# NixiePSU.net
KiCad netlist of a schematic drawn in Altium Designer
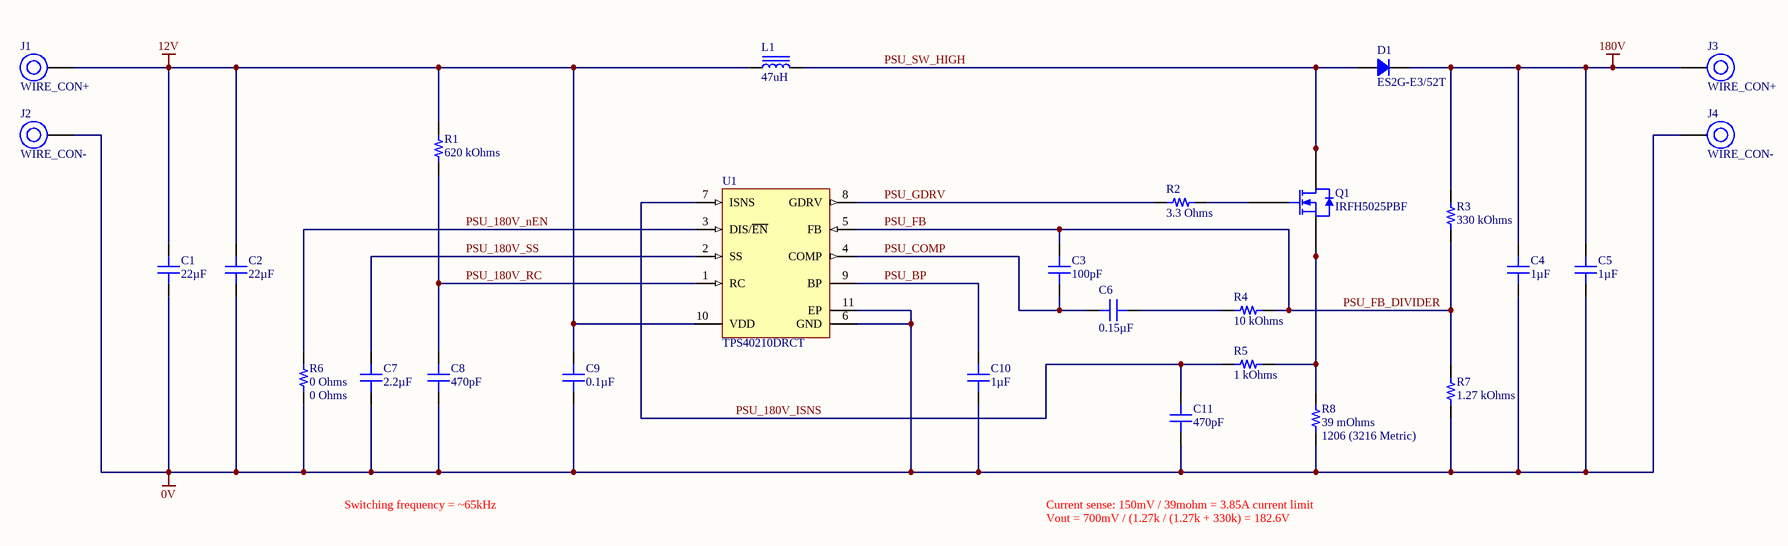
[diagram p0: NixiePSU.SchDoc]

(export (version "E")
  (design (tool "Eeschema 10.0.6"))
  (components
    (comp (ref "C1")
      (value "22µF")
      (footprint "CAP 1210_3225 - 2.8MM")
      (description "CAP CER 22UF 25V X6S 1210")
      (fields (field (name "PART NUMBER") "GRM32EC81E226KE15L"))
      (libsource (lib "Celestial Altium Library - altium_library") (part "Capacitor"))
    )
    (comp (ref "C2")
      (value "22µF")
      (footprint "CAP 1210_3225 - 2.8MM")
      (description "CAP CER 22UF 25V X6S 1210")
      (fields (field (name "PART NUMBER") "GRM32EC81E226KE15L"))
      (libsource (lib "Celestial Altium Library - altium_library") (part "Capacitor"))
    )
    (comp (ref "C3")
      (value "100pF")
      (footprint "CAP 0603_1608")
      (description "CAP CER 100PF 16V NP0 0603")
      (fields (field (name "PART NUMBER") "C0603C101K4GAC7867") (field (name "MANUFACTURER") "KEMET"))
      (libsource (lib "Celestial Altium Library - altium_library") (part "Capacitor"))
    )
    (comp (ref "C4")
      (value "1µF")
      (footprint "CAP 2220_5650 2.0MM")
      (description "CAP CER 1UF 250V X7R 2220")
      (fields (field (name "PART NUMBER") "C2220C105KARACTU") (field (name "MANUFACTURER") "KEMET"))
      (libsource (lib "Celestial Altium Library - altium_library") (part "Capacitor"))
    )
    (comp (ref "C5")
      (value "1µF")
      (footprint "CAP 2220_5650 2.0MM")
      (description "CAP CER 1UF 250V X7R 2220")
      (fields (field (name "PART NUMBER") "C2220C105KARACTU") (field (name "MANUFACTURER") "KEMET"))
      (libsource (lib "Celestial Altium Library - altium_library") (part "Capacitor"))
    )
    (comp (ref "C6")
      (value "0.15µF")
      (footprint "CAP 0603_1608")
      (description "CAP CER 0.15UF 16V X7R 0603")
      (fields (field (name "PART NUMBER") "CC0603KRX7R7BB154") (field (name "MANUFACTURER") "Yageo"))
      (libsource (lib "Celestial Altium Library - altium_library") (part "Capacitor"))
    )
    (comp (ref "C7")
      (value "2.2µF")
      (footprint "CAP 0603_1608")
      (description "CAP CER 2.2UF 50V X5R 0603")
      (fields (field (name "PART NUMBER") "GRM188R61H225KE11D"))
      (libsource (lib "Celestial Altium Library - altium_library") (part "Capacitor"))
    )
    (comp (ref "C8")
      (value "470pF")
      (footprint "CAP 0603_1608")
      (description "CAP CER 470PF 50V C0G 0603")
      (fields (field (name "PART NUMBER") "CGJ3E2C0G1H471J080AA"))
      (libsource (lib "Celestial Altium Library - altium_library") (part "Capacitor"))
    )
    (comp (ref "C9")
      (value "0.1µF")
      (footprint "CAP 0603_1608")
      (description "CAP CER 0.1UF 25V X5R 0603")
      (fields (field (name "PART NUMBER") "C0603C104K3PAC7867") (field (name "MANUFACTURER") "KEMET"))
      (libsource (lib "Celestial Altium Library - altium_library") (part "Capacitor"))
    )
    (comp (ref "C10")
      (value "1µF")
      (footprint "CAP 0603_1608")
      (description "CAP CER 1UF 25V X7R 0603")
      (fields
        (field (name "PART NUMBER") "CGJ3E1X7R1E105K080AC")
        (field (name "MANUFACTURER") "TDK Corporation")
      )
      (libsource (lib "Celestial Altium Library - altium_library") (part "Capacitor"))
    )
    (comp (ref "C11")
      (value "470pF")
      (footprint "CAP 0603_1608")
      (description "CAP CER 470PF 50V C0G 0603")
      (fields (field (name "PART NUMBER") "CGJ3E2C0G1H471J080AA"))
      (libsource (lib "Celestial Altium Library - altium_library") (part "Capacitor"))
    )
    (comp (ref "D1")
      (value "ES2G-E3/52T")
      (footprint "DO214AA SMB")
      (description "DIODE GEN PURP 400V 2A DO214AA")
      (fields (field (name "MANUFACTURER") "Vishay Semiconductor Diodes Division"))
      (libsource (lib "Celestial Altium Library - altium_library") (part "Diode"))
    )
    (comp (ref "J1")
      (value "WIRE_CON+")
      (footprint "WIRE_PAD+")
      (description "Wire pad connection")
      (libsource (lib "Connectors") (part "WIRE_CON+"))
    )
    (comp (ref "J2")
      (value "WIRE_CON-")
      (footprint "WIRE_PAD-")
      (description "Wire pad connection")
      (libsource (lib "Connectors") (part "WIRE_CON-"))
    )
    (comp (ref "J3")
      (value "WIRE_CON+")
      (footprint "WIRE_PAD+")
      (description "Wire pad connection")
      (libsource (lib "Connectors") (part "WIRE_CON+"))
    )
    (comp (ref "J4")
      (value "WIRE_CON-")
      (footprint "WIRE_PAD-")
      (description "Wire pad connection")
      (libsource (lib "Connectors") (part "WIRE_CON-"))
    )
    (comp (ref "L1")
      (value "47uH")
      (footprint "SRP1040VA")
      (description "FIXED IND 47UH 4A 167MOHM SMD")
      (libsource (lib "NixiePSU") (part "SRP1040VA-470M"))
    )
    (comp (ref "Q1")
      (value "IRFH5025PBF")
      (footprint "QFN127P600X500X80_HS-9M")
      (description "IRFH5025TRPBF -  MOSFET Transistor, N Channel, 25 A, 250 V, 0.084 ohm, 10 V, 5 V")
      (libsource (lib "Transistors") (part "IRFH5025PBF N Channel FET"))
    )
    (comp (ref "R1")
      (value "620 kOhms")
      (footprint "RES 0603_1608")
      (description "RES SMD 620K OHM 1% 1/10W 0603")
      (fields (field (name "PART NUMBER") "ERJ-3EKF6203V"))
      (libsource (lib "Celestial Altium Library - altium_library") (part "Resistor"))
    )
    (comp (ref "R2")
      (value "3.3 Ohms")
      (footprint "RES 0603_1608")
      (description "RES SMD 3.3 OHM 1% 1/10W 0603")
      (fields
        (field (name "PART NUMBER") "ERJ-3RQF3R3V")
        (field (name "MANUFACTURER") "Panasonic Electronic Components")
      )
      (libsource (lib "Celestial Altium Library - altium_library") (part "Resistor"))
    )
    (comp (ref "R3")
      (value "330 kOhms")
      (footprint "RES 0603_1608")
      (description "RES SMD 330K OHM 1% 1/10W 0603")
      (fields
        (field (name "PART NUMBER") "ERJ-3EKF3303V")
        (field (name "MANUFACTURER") "Panasonic Electronic Components")
      )
      (libsource (lib "Celestial Altium Library - altium_library") (part "Resistor"))
    )
    (comp (ref "R4")
      (value "10 kOhms")
      (footprint "RES 0603_1608")
      (description "RES SMD 10K OHM 1% 1/10W 0603")
      (fields
        (field (name "PART NUMBER") "ERJ-3EKF1002V")
        (field (name "MANUFACTURER") "Panasonic Electronic Components")
      )
      (libsource (lib "Celestial Altium Library - altium_library") (part "Resistor"))
    )
    (comp (ref "R5")
      (value "1 kOhms")
      (footprint "RES 0603_1608")
      (description "RES SMD 1K OHM 1% 1/10W 0603")
      (fields
        (field (name "PART NUMBER") "ERJ-3EKF1001V")
        (field (name "MANUFACTURER") "Panasonic Electronic Components")
      )
      (libsource (lib "Celestial Altium Library - altium_library") (part "Resistor"))
    )
    (comp (ref "R6")
      (value "0 Ohms")
      (footprint "RES 0603_1608")
      (description "RES 0 OHM JUMPER 0.01W 0603")
      (fields (field (name "PART NUMBER") "CR0603-J/-000EAS") (field (name "ALTIUM_VALUE") "0 Ohms"))
      (libsource (lib "Celestial Altium Library - altium_library") (part "Resistor"))
    )
    (comp (ref "R7")
      (value "1.27 kOhms")
      (footprint "RES 0603_1608")
      (description "RES SMD 1.27K OHM 1% 1/10W 0603")
      (fields
        (field (name "PART NUMBER") "ERJ-3EKF1271V")
        (field (name "MANUFACTURER") "Panasonic Electronic Components")
      )
      (libsource (lib "Celestial Altium Library - altium_library") (part "Resistor"))
    )
    (comp (ref "R8")
      (value "39 mOhms")
      (footprint "STACKPOLE CSR1206")
      (description "RES 0.039 OHM 1% 1W 1206")
      (fields
        (field (name "PART NUMBER") "ERJ-8BWFR039V")
        (field (name "PACKAGE / CASE") "1206 (3216 Metric)")
        (field (name "MANUFACTURER") "Panasonic Electronic Components")
      )
      (libsource (lib "Celestial Altium Library - altium_library") (part "Resistor"))
    )
    (comp (ref "U1")
      (value "TPS40210DRCT")
      (footprint "DRC0010A_V")
      (fields (field (name "MANUFACTURER") "Texas Instruments"))
      (libsource (lib "Altium Content Vault") (part "TI-TPS40210DRC10-2400X1650TP"))
    )
  )
  (nets
    (net (code "1") (name "/PSU_180V_ISNS") (class "Default")
      (node (ref "C11") (pin "2") (pinfunction "2_2") (pintype "passive"))
      (node (ref "R5") (pin "1") (pinfunction "1_1") (pintype "passive"))
      (node (ref "U1") (pin "7") (pinfunction "ISNS_7") (pintype "input"))
    )
    (net (code "2") (name "/PSU_180V_RC") (class "Default")
      (node (ref "C8") (pin "2") (pinfunction "2_2") (pintype "passive"))
      (node (ref "R1") (pin "1") (pinfunction "1_1") (pintype "passive"))
      (node (ref "U1") (pin "1") (pinfunction "RC_1") (pintype "input"))
    )
    (net (code "3") (name "/PSU_180V_SS") (class "Default")
      (node (ref "C7") (pin "2") (pinfunction "2_2") (pintype "passive"))
      (node (ref "U1") (pin "2") (pinfunction "SS_2") (pintype "input"))
    )
    (net (code "4") (name "/PSU_180V_nEN") (class "Default")
      (node (ref "R6") (pin "2") (pinfunction "2_2") (pintype "passive"))
      (node (ref "U1") (pin "3") (pinfunction "DIS/~{EN}_3") (pintype "input"))
    )
    (net (code "5") (name "/PSU_BP") (class "Default")
      (node (ref "C10") (pin "2") (pinfunction "2_2") (pintype "passive"))
      (node (ref "U1") (pin "9") (pinfunction "BP_9") (pintype "power_in"))
    )
    (net (code "6") (name "/PSU_COMP") (class "Default")
      (node (ref "C3") (pin "2") (pinfunction "2_2") (pintype "passive"))
      (node (ref "C6") (pin "1") (pinfunction "1_1") (pintype "passive"))
      (node (ref "U1") (pin "4") (pinfunction "COMP_4") (pintype "output"))
    )
    (net (code "7") (name "/PSU_FB") (class "Default")
      (node (ref "C3") (pin "1") (pinfunction "1_1") (pintype "passive"))
      (node (ref "R3") (pin "1") (pinfunction "1_1") (pintype "passive"))
      (node (ref "R4") (pin "2") (pinfunction "2_2") (pintype "passive"))
      (node (ref "R7") (pin "2") (pinfunction "2_2") (pintype "passive"))
      (node (ref "U1") (pin "5") (pinfunction "FB_5") (pintype "input"))
    )
    (net (code "8") (name "/PSU_GDRV") (class "Default")
      (node (ref "R2") (pin "1") (pinfunction "1_1") (pintype "passive"))
      (node (ref "U1") (pin "8") (pinfunction "GDRV_8") (pintype "output"))
    )
    (net (code "9") (name "/PSU_SW_HIGH") (class "Default")
      (node (ref "D1") (pin "1") (pinfunction "1_1") (pintype "passive"))
      (node (ref "L1") (pin "2") (pinfunction "2_2") (pintype "passive"))
      (node (ref "Q1") (pin "5") (pinfunction "D_5") (pintype "passive"))
      (node (ref "Q1") (pin "6") (pinfunction "D_6") (pintype "passive"))
      (node (ref "Q1") (pin "7") (pinfunction "D_7") (pintype "passive"))
      (node (ref "Q1") (pin "8") (pinfunction "D_8") (pintype "passive"))
      (node (ref "Q1") (pin "9") (pinfunction "D_9") (pintype "passive"))
    )
    (net (code "10") (name "0V") (class "Default")
      (node (ref "C1") (pin "1") (pinfunction "1_1") (pintype "passive"))
      (node (ref "C10") (pin "1") (pinfunction "1_1") (pintype "passive"))
      (node (ref "C11") (pin "1") (pinfunction "1_1") (pintype "passive"))
      (node (ref "C2") (pin "1") (pinfunction "1_1") (pintype "passive"))
      (node (ref "C4") (pin "1") (pinfunction "1_1") (pintype "passive"))
      (node (ref "C5") (pin "1") (pinfunction "1_1") (pintype "passive"))
      (node (ref "C7") (pin "1") (pinfunction "1_1") (pintype "passive"))
      (node (ref "C8") (pin "1") (pinfunction "1_1") (pintype "passive"))
      (node (ref "C9") (pin "1") (pinfunction "1_1") (pintype "passive"))
      (node (ref "J2") (pin "1") (pinfunction "1_1") (pintype "passive"))
      (node (ref "J4") (pin "1") (pinfunction "1_1") (pintype "passive"))
      (node (ref "R6") (pin "1") (pinfunction "1_1") (pintype "passive"))
      (node (ref "R7") (pin "1") (pinfunction "1_1") (pintype "passive"))
      (node (ref "R8") (pin "1") (pinfunction "1_1") (pintype "passive"))
      (node (ref "U1") (pin "11") (pinfunction "EP_11") (pintype "passive"))
      (node (ref "U1") (pin "6") (pinfunction "GND_6") (pintype "power_in"))
    )
    (net (code "11") (name "12V") (class "Default")
      (node (ref "C1") (pin "2") (pinfunction "2_2") (pintype "passive"))
      (node (ref "C2") (pin "2") (pinfunction "2_2") (pintype "passive"))
      (node (ref "C9") (pin "2") (pinfunction "2_2") (pintype "passive"))
      (node (ref "J1") (pin "1") (pinfunction "1_1") (pintype "passive"))
      (node (ref "L1") (pin "1") (pinfunction "1_1") (pintype "passive"))
      (node (ref "R1") (pin "2") (pinfunction "2_2") (pintype "passive"))
      (node (ref "U1") (pin "10") (pinfunction "VDD_10") (pintype "power_in"))
    )
    (net (code "12") (name "180V") (class "Default")
      (node (ref "C4") (pin "2") (pinfunction "2_2") (pintype "passive"))
      (node (ref "C5") (pin "2") (pinfunction "2_2") (pintype "passive"))
      (node (ref "D1") (pin "2") (pinfunction "2_2") (pintype "passive"))
      (node (ref "J3") (pin "1") (pinfunction "1_1") (pintype "passive"))
      (node (ref "R3") (pin "2") (pinfunction "2_2") (pintype "passive"))
    )
    (net (code "13") (name "Net-(C6-Pad2)") (class "Default")
      (node (ref "C6") (pin "2") (pinfunction "2_2") (pintype "passive"))
      (node (ref "R4") (pin "1") (pinfunction "1_1") (pintype "passive"))
    )
    (net (code "14") (name "Net-(Q1-G)") (class "Default")
      (node (ref "Q1") (pin "4") (pinfunction "G_4") (pintype "passive"))
      (node (ref "R2") (pin "2") (pinfunction "2_2") (pintype "passive"))
    )
    (net (code "15") (name "Net-(Q1-S-Pad1)") (class "Default")
      (node (ref "Q1") (pin "1") (pinfunction "S_1") (pintype "passive"))
      (node (ref "Q1") (pin "2") (pinfunction "S_2") (pintype "passive"))
      (node (ref "Q1") (pin "3") (pinfunction "S_3") (pintype "passive"))
      (node (ref "R5") (pin "2") (pinfunction "2_2") (pintype "passive"))
      (node (ref "R8") (pin "2") (pinfunction "2_2") (pintype "passive"))
    )
  )
)
